# Customer_Module-Main_Connector.net
KiCad netlist of a schematic drawn in Altium Designer
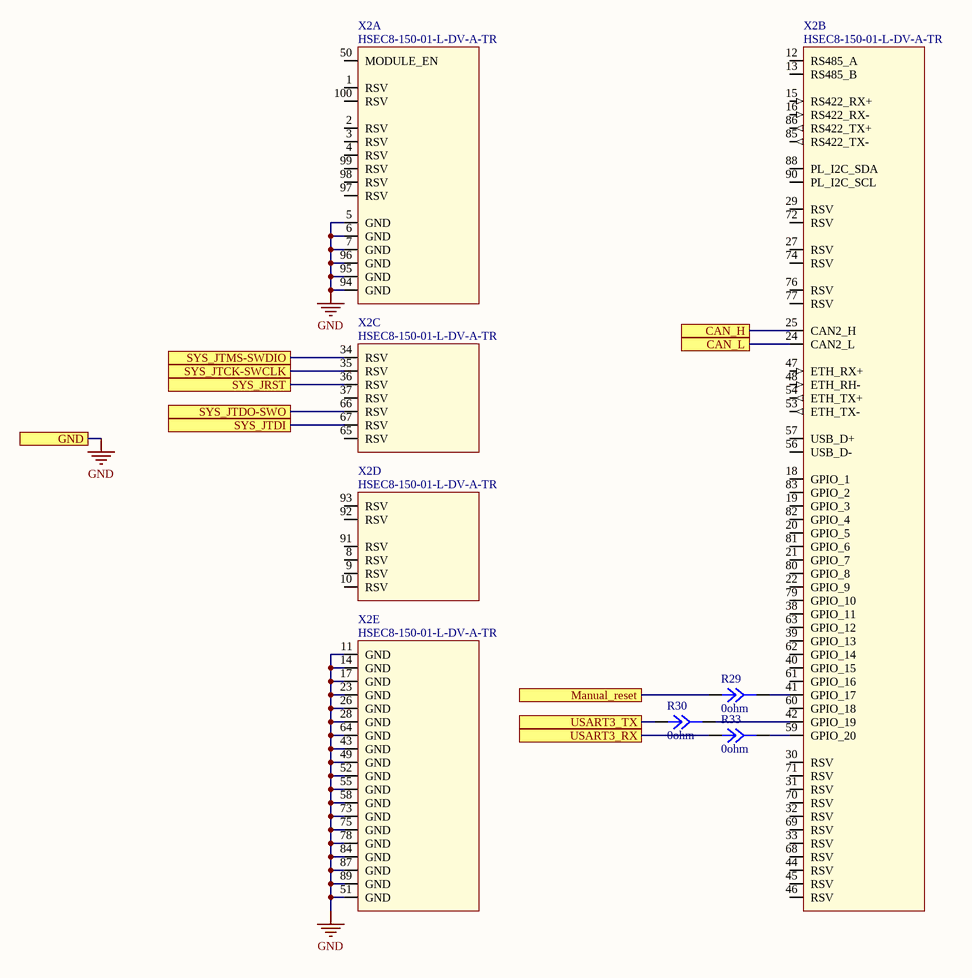
[diagram p0: Customer_Module-Main_Connector.SchDoc]

(export (version "E")
  (design (tool "Eeschema 10.0.6"))
  (components
    (comp (ref "R29")
      (value "0ohm")
      (footprint "Jumper 2")
      (libsource (lib "Cubesat_lib") (part "Mini jumper"))
    )
    (comp (ref "R30")
      (value "0ohm")
      (footprint "Jumper 2")
      (libsource (lib "Cubesat_lib") (part "Mini jumper"))
    )
    (comp (ref "R33")
      (value "0ohm")
      (footprint "Jumper 2")
      (libsource (lib "Cubesat_lib") (part "Mini jumper"))
    )
    (comp (ref "X2")
      (value "HSEC8-150-01-L-DV-A-TR")
      (footprint "HSEC8-150-01-L-DV-A-TR")
      (libsource (lib "HSEC8-150-01-L-DV-A-TR") (part "HSEC8-150-01-L-DV-A-TR"))
    )
  )
  (nets
    (net (code "1") (name "/CAN_H") (class "Default")
      (node (ref "X2") (pin "25") (pinfunction "CAN2_H_25") (pintype "bidirectional"))
    )
    (net (code "2") (name "/CAN_L") (class "Default")
      (node (ref "X2") (pin "24") (pinfunction "CAN2_L_24") (pintype "bidirectional"))
    )
    (net (code "3") (name "/Manual_reset") (class "Default")
      (node (ref "R29") (pin "1") (pinfunction "1_1") (pintype "passive"))
    )
    (net (code "4") (name "/SYS_JRST") (class "Default")
      (node (ref "X2") (pin "36") (pinfunction "RSV_36") (pintype "passive"))
    )
    (net (code "5") (name "/SYS_JTCK-SWCLK") (class "Default")
      (node (ref "X2") (pin "35") (pinfunction "RSV_35") (pintype "passive"))
    )
    (net (code "6") (name "/SYS_JTDI") (class "Default")
      (node (ref "X2") (pin "67") (pinfunction "RSV_67") (pintype "passive"))
    )
    (net (code "7") (name "/SYS_JTDO-SWO") (class "Default")
      (node (ref "X2") (pin "66") (pinfunction "RSV_66") (pintype "passive"))
    )
    (net (code "8") (name "/SYS_JTMS-SWDIO") (class "Default")
      (node (ref "X2") (pin "34") (pinfunction "RSV_34") (pintype "passive"))
    )
    (net (code "9") (name "/USART3_RX") (class "Default")
      (node (ref "R33") (pin "1") (pinfunction "1_1") (pintype "passive"))
    )
    (net (code "10") (name "/USART3_TX") (class "Default")
      (node (ref "R30") (pin "1") (pinfunction "1_1") (pintype "passive"))
    )
    (net (code "11") (name "GND") (class "Default")
      (node (ref "X2") (pin "11") (pinfunction "GND_11") (pintype "power_in"))
      (node (ref "X2") (pin "14") (pinfunction "GND_14") (pintype "power_in"))
      (node (ref "X2") (pin "17") (pinfunction "GND_17") (pintype "power_in"))
      (node (ref "X2") (pin "23") (pinfunction "GND_23") (pintype "power_in"))
      (node (ref "X2") (pin "26") (pinfunction "GND_26") (pintype "power_in"))
      (node (ref "X2") (pin "28") (pinfunction "GND_28") (pintype "power_in"))
      (node (ref "X2") (pin "43") (pinfunction "GND_43") (pintype "power_in"))
      (node (ref "X2") (pin "49") (pinfunction "GND_49") (pintype "power_in"))
      (node (ref "X2") (pin "5") (pinfunction "GND_5") (pintype "power_in"))
      (node (ref "X2") (pin "51") (pinfunction "GND_51") (pintype "power_in"))
      (node (ref "X2") (pin "52") (pinfunction "GND_52") (pintype "power_in"))
      (node (ref "X2") (pin "55") (pinfunction "GND_55") (pintype "power_in"))
      (node (ref "X2") (pin "58") (pinfunction "GND_58") (pintype "power_in"))
      (node (ref "X2") (pin "6") (pinfunction "GND_6") (pintype "power_in"))
      (node (ref "X2") (pin "64") (pinfunction "GND_64") (pintype "power_in"))
      (node (ref "X2") (pin "7") (pinfunction "GND_7") (pintype "power_in"))
      (node (ref "X2") (pin "73") (pinfunction "GND_73") (pintype "power_in"))
      (node (ref "X2") (pin "75") (pinfunction "GND_75") (pintype "power_in"))
      (node (ref "X2") (pin "78") (pinfunction "GND_78") (pintype "power_in"))
      (node (ref "X2") (pin "84") (pinfunction "GND_84") (pintype "power_in"))
      (node (ref "X2") (pin "87") (pinfunction "GND_87") (pintype "power_in"))
      (node (ref "X2") (pin "89") (pinfunction "GND_89") (pintype "power_in"))
      (node (ref "X2") (pin "94") (pinfunction "GND_94") (pintype "power_in"))
      (node (ref "X2") (pin "95") (pinfunction "GND_95") (pintype "power_in"))
      (node (ref "X2") (pin "96") (pinfunction "GND_96") (pintype "power_in"))
    )
    (net (code "12") (name "Net-(X2B-GPIO_17)") (class "Default")
      (node (ref "R29") (pin "2") (pinfunction "2_2") (pintype "passive"))
      (node (ref "X2") (pin "41") (pinfunction "GPIO_17_41") (pintype "bidirectional"))
    )
    (net (code "13") (name "Net-(X2B-GPIO_19)") (class "Default")
      (node (ref "R30") (pin "2") (pinfunction "2_2") (pintype "passive"))
      (node (ref "X2") (pin "42") (pinfunction "GPIO_19_42") (pintype "bidirectional"))
    )
    (net (code "14") (name "Net-(X2B-GPIO_20)") (class "Default")
      (node (ref "R33") (pin "2") (pinfunction "2_2") (pintype "passive"))
      (node (ref "X2") (pin "59") (pinfunction "GPIO_20_59") (pintype "bidirectional"))
    )
    (net (code "15") (name "unconnected-(X2A-MODULE_EN-Pad50)") (class "Default")
      (node (ref "X2") (pin "50") (pinfunction "MODULE_EN_50") (pintype "bidirectional"))
    )
    (net (code "16") (name "unconnected-(X2A-RSV-Pad1)") (class "Default")
      (node (ref "X2") (pin "1") (pinfunction "RSV_1") (pintype "passive"))
    )
    (net (code "17") (name "unconnected-(X2A-RSV-Pad2)") (class "Default")
      (node (ref "X2") (pin "2") (pinfunction "RSV_2") (pintype "power_in"))
    )
    (net (code "18") (name "unconnected-(X2A-RSV-Pad3)") (class "Default")
      (node (ref "X2") (pin "3") (pinfunction "RSV_3") (pintype "power_in"))
    )
    (net (code "19") (name "unconnected-(X2A-RSV-Pad4)") (class "Default")
      (node (ref "X2") (pin "4") (pinfunction "RSV_4") (pintype "power_in"))
    )
    (net (code "20") (name "unconnected-(X2A-RSV-Pad97)") (class "Default")
      (node (ref "X2") (pin "97") (pinfunction "RSV_97") (pintype "power_in"))
    )
    (net (code "21") (name "unconnected-(X2A-RSV-Pad98)") (class "Default")
      (node (ref "X2") (pin "98") (pinfunction "RSV_98") (pintype "power_in"))
    )
    (net (code "22") (name "unconnected-(X2A-RSV-Pad99)") (class "Default")
      (node (ref "X2") (pin "99") (pinfunction "RSV_99") (pintype "power_in"))
    )
    (net (code "23") (name "unconnected-(X2A-RSV-Pad100)") (class "Default")
      (node (ref "X2") (pin "100") (pinfunction "RSV_100") (pintype "passive"))
    )
    (net (code "24") (name "unconnected-(X2B-ETH_RH--Pad48)") (class "Default")
      (node (ref "X2") (pin "48") (pinfunction "ETH_RH-_48") (pintype "input"))
    )
    (net (code "25") (name "unconnected-(X2B-ETH_RX+-Pad47)") (class "Default")
      (node (ref "X2") (pin "47") (pinfunction "ETH_RX+_47") (pintype "input"))
    )
    (net (code "26") (name "unconnected-(X2B-ETH_TX+-Pad54)") (class "Default")
      (node (ref "X2") (pin "54") (pinfunction "ETH_TX+_54") (pintype "output"))
    )
    (net (code "27") (name "unconnected-(X2B-ETH_TX--Pad53)") (class "Default")
      (node (ref "X2") (pin "53") (pinfunction "ETH_TX-_53") (pintype "output"))
    )
    (net (code "28") (name "unconnected-(X2B-GPIO_1-Pad18)") (class "Default")
      (node (ref "X2") (pin "18") (pinfunction "GPIO_1_18") (pintype "bidirectional"))
    )
    (net (code "29") (name "unconnected-(X2B-GPIO_2-Pad83)") (class "Default")
      (node (ref "X2") (pin "83") (pinfunction "GPIO_2_83") (pintype "bidirectional"))
    )
    (net (code "30") (name "unconnected-(X2B-GPIO_3-Pad19)") (class "Default")
      (node (ref "X2") (pin "19") (pinfunction "GPIO_3_19") (pintype "bidirectional"))
    )
    (net (code "31") (name "unconnected-(X2B-GPIO_4-Pad82)") (class "Default")
      (node (ref "X2") (pin "82") (pinfunction "GPIO_4_82") (pintype "bidirectional"))
    )
    (net (code "32") (name "unconnected-(X2B-GPIO_5-Pad20)") (class "Default")
      (node (ref "X2") (pin "20") (pinfunction "GPIO_5_20") (pintype "bidirectional"))
    )
    (net (code "33") (name "unconnected-(X2B-GPIO_6-Pad81)") (class "Default")
      (node (ref "X2") (pin "81") (pinfunction "GPIO_6_81") (pintype "bidirectional"))
    )
    (net (code "34") (name "unconnected-(X2B-GPIO_7-Pad21)") (class "Default")
      (node (ref "X2") (pin "21") (pinfunction "GPIO_7_21") (pintype "bidirectional"))
    )
    (net (code "35") (name "unconnected-(X2B-GPIO_8-Pad80)") (class "Default")
      (node (ref "X2") (pin "80") (pinfunction "GPIO_8_80") (pintype "bidirectional"))
    )
    (net (code "36") (name "unconnected-(X2B-GPIO_9-Pad22)") (class "Default")
      (node (ref "X2") (pin "22") (pinfunction "GPIO_9_22") (pintype "bidirectional"))
    )
    (net (code "37") (name "unconnected-(X2B-GPIO_10-Pad79)") (class "Default")
      (node (ref "X2") (pin "79") (pinfunction "GPIO_10_79") (pintype "bidirectional"))
    )
    (net (code "38") (name "unconnected-(X2B-GPIO_11-Pad38)") (class "Default")
      (node (ref "X2") (pin "38") (pinfunction "GPIO_11_38") (pintype "bidirectional"))
    )
    (net (code "39") (name "unconnected-(X2B-GPIO_12-Pad63)") (class "Default")
      (node (ref "X2") (pin "63") (pinfunction "GPIO_12_63") (pintype "bidirectional"))
    )
    (net (code "40") (name "unconnected-(X2B-GPIO_13-Pad39)") (class "Default")
      (node (ref "X2") (pin "39") (pinfunction "GPIO_13_39") (pintype "bidirectional"))
    )
    (net (code "41") (name "unconnected-(X2B-GPIO_14-Pad62)") (class "Default")
      (node (ref "X2") (pin "62") (pinfunction "GPIO_14_62") (pintype "bidirectional"))
    )
    (net (code "42") (name "unconnected-(X2B-GPIO_15-Pad40)") (class "Default")
      (node (ref "X2") (pin "40") (pinfunction "GPIO_15_40") (pintype "bidirectional"))
    )
    (net (code "43") (name "unconnected-(X2B-GPIO_16-Pad61)") (class "Default")
      (node (ref "X2") (pin "61") (pinfunction "GPIO_16_61") (pintype "bidirectional"))
    )
    (net (code "44") (name "unconnected-(X2B-GPIO_18-Pad60)") (class "Default")
      (node (ref "X2") (pin "60") (pinfunction "GPIO_18_60") (pintype "bidirectional"))
    )
    (net (code "45") (name "unconnected-(X2B-PL_I2C_SCL-Pad90)") (class "Default")
      (node (ref "X2") (pin "90") (pinfunction "PL_I2C_SCL_90") (pintype "passive"))
    )
    (net (code "46") (name "unconnected-(X2B-PL_I2C_SDA-Pad88)") (class "Default")
      (node (ref "X2") (pin "88") (pinfunction "PL_I2C_SDA_88") (pintype "bidirectional"))
    )
    (net (code "47") (name "unconnected-(X2B-RS422_RX+-Pad15)") (class "Default")
      (node (ref "X2") (pin "15") (pinfunction "RS422_RX+_15") (pintype "input"))
    )
    (net (code "48") (name "unconnected-(X2B-RS422_RX--Pad16)") (class "Default")
      (node (ref "X2") (pin "16") (pinfunction "RS422_RX-_16") (pintype "input"))
    )
    (net (code "49") (name "unconnected-(X2B-RS422_TX+-Pad86)") (class "Default")
      (node (ref "X2") (pin "86") (pinfunction "RS422_TX+_86") (pintype "output"))
    )
    (net (code "50") (name "unconnected-(X2B-RS422_TX--Pad85)") (class "Default")
      (node (ref "X2") (pin "85") (pinfunction "RS422_TX-_85") (pintype "output"))
    )
    (net (code "51") (name "unconnected-(X2B-RS485_A-Pad12)") (class "Default")
      (node (ref "X2") (pin "12") (pinfunction "RS485_A_12") (pintype "bidirectional"))
    )
    (net (code "52") (name "unconnected-(X2B-RS485_B-Pad13)") (class "Default")
      (node (ref "X2") (pin "13") (pinfunction "RS485_B_13") (pintype "bidirectional"))
    )
    (net (code "53") (name "unconnected-(X2B-RSV-Pad27)") (class "Default")
      (node (ref "X2") (pin "27") (pinfunction "RSV_27") (pintype "passive"))
    )
    (net (code "54") (name "unconnected-(X2B-RSV-Pad29)") (class "Default")
      (node (ref "X2") (pin "29") (pinfunction "RSV_29") (pintype "passive"))
    )
    (net (code "55") (name "unconnected-(X2B-RSV-Pad30)") (class "Default")
      (node (ref "X2") (pin "30") (pinfunction "RSV_30") (pintype "passive"))
    )
    (net (code "56") (name "unconnected-(X2B-RSV-Pad31)") (class "Default")
      (node (ref "X2") (pin "31") (pinfunction "RSV_31") (pintype "passive"))
    )
    (net (code "57") (name "unconnected-(X2B-RSV-Pad32)") (class "Default")
      (node (ref "X2") (pin "32") (pinfunction "RSV_32") (pintype "passive"))
    )
    (net (code "58") (name "unconnected-(X2B-RSV-Pad33)") (class "Default")
      (node (ref "X2") (pin "33") (pinfunction "RSV_33") (pintype "passive"))
    )
    (net (code "59") (name "unconnected-(X2B-RSV-Pad44)") (class "Default")
      (node (ref "X2") (pin "44") (pinfunction "RSV_44") (pintype "passive"))
    )
    (net (code "60") (name "unconnected-(X2B-RSV-Pad45)") (class "Default")
      (node (ref "X2") (pin "45") (pinfunction "RSV_45") (pintype "passive"))
    )
    (net (code "61") (name "unconnected-(X2B-RSV-Pad46)") (class "Default")
      (node (ref "X2") (pin "46") (pinfunction "RSV_46") (pintype "passive"))
    )
    (net (code "62") (name "unconnected-(X2B-RSV-Pad68)") (class "Default")
      (node (ref "X2") (pin "68") (pinfunction "RSV_68") (pintype "passive"))
    )
    (net (code "63") (name "unconnected-(X2B-RSV-Pad69)") (class "Default")
      (node (ref "X2") (pin "69") (pinfunction "RSV_69") (pintype "passive"))
    )
    (net (code "64") (name "unconnected-(X2B-RSV-Pad70)") (class "Default")
      (node (ref "X2") (pin "70") (pinfunction "RSV_70") (pintype "passive"))
    )
    (net (code "65") (name "unconnected-(X2B-RSV-Pad71)") (class "Default")
      (node (ref "X2") (pin "71") (pinfunction "RSV_71") (pintype "passive"))
    )
    (net (code "66") (name "unconnected-(X2B-RSV-Pad72)") (class "Default")
      (node (ref "X2") (pin "72") (pinfunction "RSV_72") (pintype "passive"))
    )
    (net (code "67") (name "unconnected-(X2B-RSV-Pad74)") (class "Default")
      (node (ref "X2") (pin "74") (pinfunction "RSV_74") (pintype "passive"))
    )
    (net (code "68") (name "unconnected-(X2B-RSV-Pad76)") (class "Default")
      (node (ref "X2") (pin "76") (pinfunction "RSV_76") (pintype "passive"))
    )
    (net (code "69") (name "unconnected-(X2B-RSV-Pad77)") (class "Default")
      (node (ref "X2") (pin "77") (pinfunction "RSV_77") (pintype "passive"))
    )
    (net (code "70") (name "unconnected-(X2B-USB_D+-Pad57)") (class "Default")
      (node (ref "X2") (pin "57") (pinfunction "USB_D+_57") (pintype "bidirectional"))
    )
    (net (code "71") (name "unconnected-(X2B-USB_D--Pad56)") (class "Default")
      (node (ref "X2") (pin "56") (pinfunction "USB_D-_56") (pintype "bidirectional"))
    )
    (net (code "72") (name "unconnected-(X2C-RSV-Pad37)") (class "Default")
      (node (ref "X2") (pin "37") (pinfunction "RSV_37") (pintype "power_in"))
    )
    (net (code "73") (name "unconnected-(X2C-RSV-Pad65)") (class "Default")
      (node (ref "X2") (pin "65") (pinfunction "RSV_65") (pintype "passive"))
    )
    (net (code "74") (name "unconnected-(X2D-RSV-Pad8)") (class "Default")
      (node (ref "X2") (pin "8") (pinfunction "RSV_8") (pintype "passive"))
    )
    (net (code "75") (name "unconnected-(X2D-RSV-Pad9)") (class "Default")
      (node (ref "X2") (pin "9") (pinfunction "RSV_9") (pintype "passive"))
    )
    (net (code "76") (name "unconnected-(X2D-RSV-Pad10)") (class "Default")
      (node (ref "X2") (pin "10") (pinfunction "RSV_10") (pintype "passive"))
    )
    (net (code "77") (name "unconnected-(X2D-RSV-Pad91)") (class "Default")
      (node (ref "X2") (pin "91") (pinfunction "RSV_91") (pintype "passive"))
    )
    (net (code "78") (name "unconnected-(X2D-RSV-Pad92)") (class "Default")
      (node (ref "X2") (pin "92") (pinfunction "RSV_92") (pintype "power_in"))
    )
    (net (code "79") (name "unconnected-(X2D-RSV-Pad93)") (class "Default")
      (node (ref "X2") (pin "93") (pinfunction "RSV_93") (pintype "power_in"))
    )
  )
)
